# joint_board_load_cell.net
KiCad netlist of a schematic drawn in Altium Designer
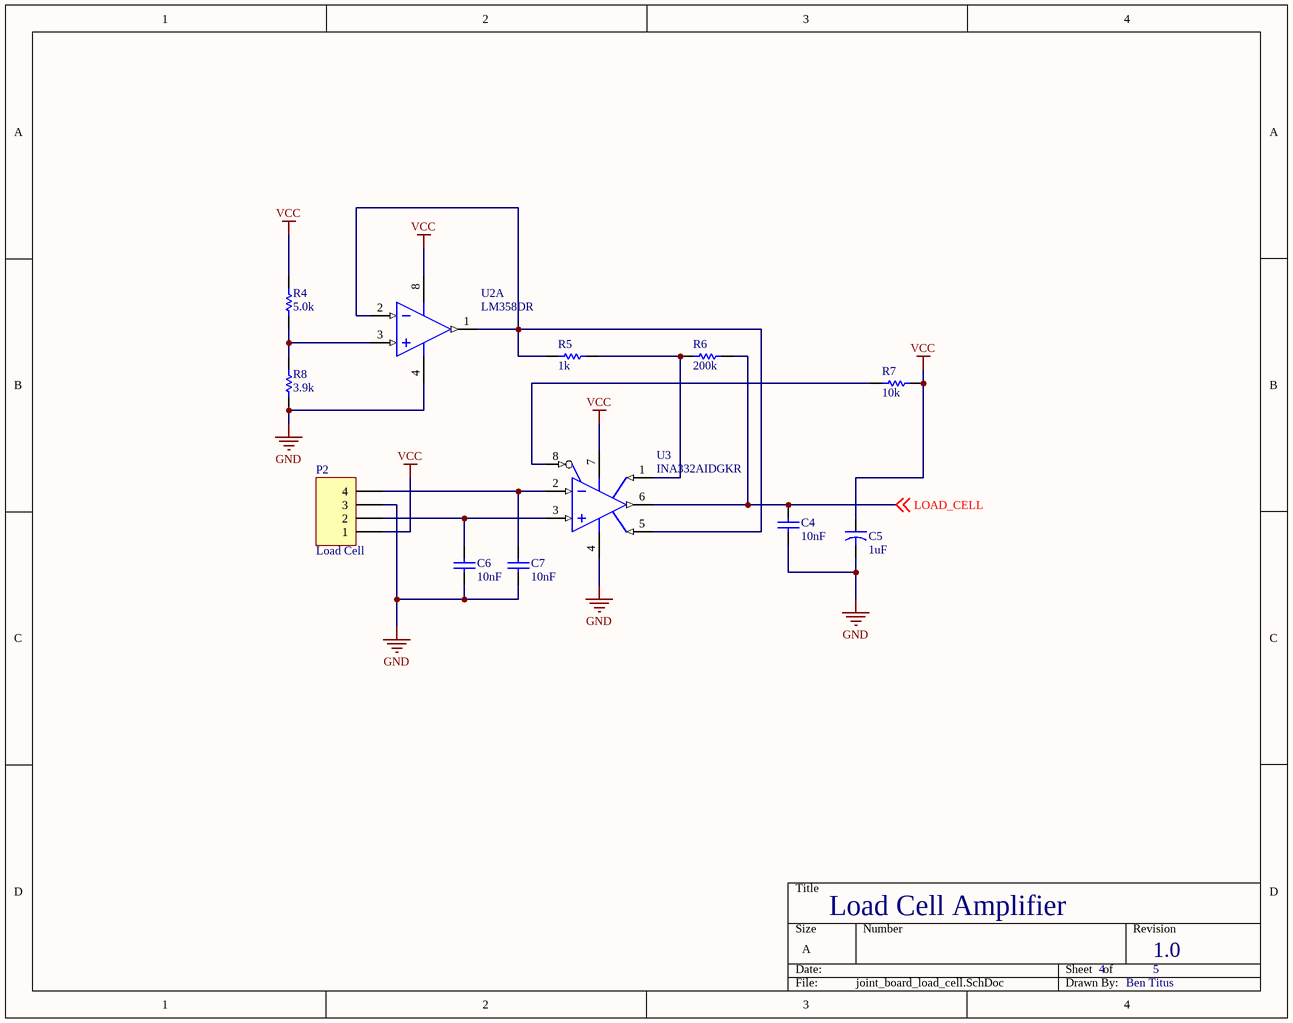
[diagram p0: joint_board_load_cell.SchDoc]

(export (version "E")
  (design (tool "Eeschema 10.0.6"))
  (components
    (comp (ref "C4")
      (value "10nF")
      (footprint "CAPC0805(2012)145_L")
      (description "0805 (2012 Metric) Chip Capacitor")
      (libsource (lib "Altium Content Vault") (part "CAP_5"))
    )
    (comp (ref "C5")
      (value "1uF")
      (footprint "CAPR5-4X5")
      (description "Capacitor")
      (fields (field (name "PUBLISHER") "Altium Limited"))
      (libsource (lib "Miscellaneous Devices") (part "Cap2"))
    )
    (comp (ref "C6")
      (value "10nF")
      (footprint "CAPC0805(2012)145_L")
      (description "0805 (2012 Metric) Chip Capacitor")
      (libsource (lib "Altium Content Vault") (part "CAP_5"))
    )
    (comp (ref "C7")
      (value "10nF")
      (footprint "CAPC0805(2012)145_L")
      (description "0805 (2012 Metric) Chip Capacitor")
      (libsource (lib "Altium Content Vault") (part "CAP_5"))
    )
    (comp (ref "P2")
      (value "Load Cell")
      (footprint "HDR1X4")
      (description "Header, 4-Pin")
      (fields (field (name "PUBLISHER") "Altium Limited"))
      (libsource (lib "Miscellaneous Connectors") (part "Header 4"))
    )
    (comp (ref "R4")
      (value "5.0k")
      (footprint "RESC0805(2012)_L")
      (description "0805 (2012 Metric) Chip Resistor")
      (libsource (lib "Altium Content Vault") (part "RES_3"))
    )
    (comp (ref "R5")
      (value "1k")
      (footprint "RESC0805(2012)_L")
      (description "0805 (2012 Metric) Chip Resistor")
      (libsource (lib "Altium Content Vault") (part "RES_3"))
    )
    (comp (ref "R6")
      (value "200k")
      (footprint "RESC0805(2012)_L")
      (description "0805 (2012 Metric) Chip Resistor")
      (libsource (lib "Altium Content Vault") (part "RES_3"))
    )
    (comp (ref "R7")
      (value "10k")
      (footprint "RESC0805(2012)_L")
      (description "0805 (2012 Metric) Chip Resistor")
      (libsource (lib "Altium Content Vault") (part "RES_3"))
    )
    (comp (ref "R8")
      (value "3.9k")
      (footprint "RESC0805(2012)_L")
      (description "0805 (2012 Metric) Chip Resistor")
      (libsource (lib "Altium Content Vault") (part "RES_3"))
    )
    (comp (ref "U2")
      (value "LM358DR")
      (footprint "D0008A_L")
      (libsource (lib "Altium Content Vault") (part "TI-LM358-8"))
    )
    (comp (ref "U3")
      (value "INA332AIDGKR")
      (footprint "DGK0008A_M")
      (fields (field (name "MANUFACTURER") "Texas Instruments"))
      (libsource (lib "Custom_Lib") (part "CMP-0944-00077-2"))
    )
  )
  (nets
    (net (code "1") (name "GND") (class "Default")
      (node (ref "C4") (pin "1") (pinfunction "1_1") (pintype "passive"))
      (node (ref "C5") (pin "2") (pinfunction "2_2") (pintype "passive"))
      (node (ref "C6") (pin "1") (pinfunction "1_1") (pintype "passive"))
      (node (ref "C7") (pin "1") (pinfunction "1_1") (pintype "passive"))
      (node (ref "P2") (pin "3") (pinfunction "3_3") (pintype "passive"))
      (node (ref "R8") (pin "1") (pinfunction "1_1") (pintype "passive"))
      (node (ref "U2") (pin "4") (pinfunction "GND_4") (pintype "power_in"))
      (node (ref "U3") (pin "4") (pinfunction "V-_4") (pintype "power_in"))
    )
    (net (code "2") (name "LOAD_CELL") (class "Default")
      (node (ref "C4") (pin "2") (pinfunction "2_2") (pintype "passive"))
      (node (ref "R6") (pin "2") (pinfunction "2_2") (pintype "passive"))
      (node (ref "U3") (pin "6") (pinfunction "VOUT_6") (pintype "output"))
    )
    (net (code "3") (name "Net-(U2A-1IN+)") (class "Default")
      (node (ref "R4") (pin "1") (pinfunction "1_1") (pintype "passive"))
      (node (ref "R8") (pin "2") (pinfunction "2_2") (pintype "passive"))
      (node (ref "U2") (pin "3") (pinfunction "1IN+_3") (pintype "input"))
    )
    (net (code "4") (name "Net-(U2A-1IN-)") (class "Default")
      (node (ref "R5") (pin "1") (pinfunction "1_1") (pintype "passive"))
      (node (ref "U2") (pin "1") (pinfunction "1OUT_1") (pintype "output"))
      (node (ref "U2") (pin "2") (pinfunction "1IN-_2") (pintype "input"))
      (node (ref "U3") (pin "5") (pinfunction "REF_5") (pintype "input"))
    )
    (net (code "5") (name "Net-(U3-RG)") (class "Default")
      (node (ref "R5") (pin "2") (pinfunction "2_2") (pintype "passive"))
      (node (ref "R6") (pin "1") (pinfunction "1_1") (pintype "passive"))
      (node (ref "U3") (pin "1") (pinfunction "RG_1") (pintype "input"))
    )
    (net (code "6") (name "Net-(U3-SHUTDOWN)") (class "Default")
      (node (ref "R7") (pin "2") (pinfunction "2_2") (pintype "passive"))
      (node (ref "U3") (pin "8") (pinfunction "SHUTDOWN_8") (pintype "input"))
    )
    (net (code "7") (name "Net-(U3-VIN+)") (class "Default")
      (node (ref "C6") (pin "2") (pinfunction "2_2") (pintype "passive"))
      (node (ref "P2") (pin "2") (pinfunction "2_2") (pintype "passive"))
      (node (ref "U3") (pin "3") (pinfunction "VIN+_3") (pintype "input"))
    )
    (net (code "8") (name "Net-(U3-VIN-)") (class "Default")
      (node (ref "C7") (pin "2") (pinfunction "2_2") (pintype "passive"))
      (node (ref "P2") (pin "4") (pinfunction "4_4") (pintype "passive"))
      (node (ref "U3") (pin "2") (pinfunction "VIN-_2") (pintype "input"))
    )
    (net (code "9") (name "VCC") (class "Default")
      (node (ref "C5") (pin "1") (pinfunction "1_1") (pintype "passive"))
      (node (ref "P2") (pin "1") (pinfunction "1_1") (pintype "passive"))
      (node (ref "R4") (pin "2") (pinfunction "2_2") (pintype "passive"))
      (node (ref "R7") (pin "1") (pinfunction "1_1") (pintype "passive"))
      (node (ref "U2") (pin "8") (pinfunction "VCC_8") (pintype "power_in"))
      (node (ref "U3") (pin "7") (pinfunction "V+_7") (pintype "power_in"))
    )
  )
)
